# buttonboard-left.net
KiCad netlist of a schematic drawn in EAGLE
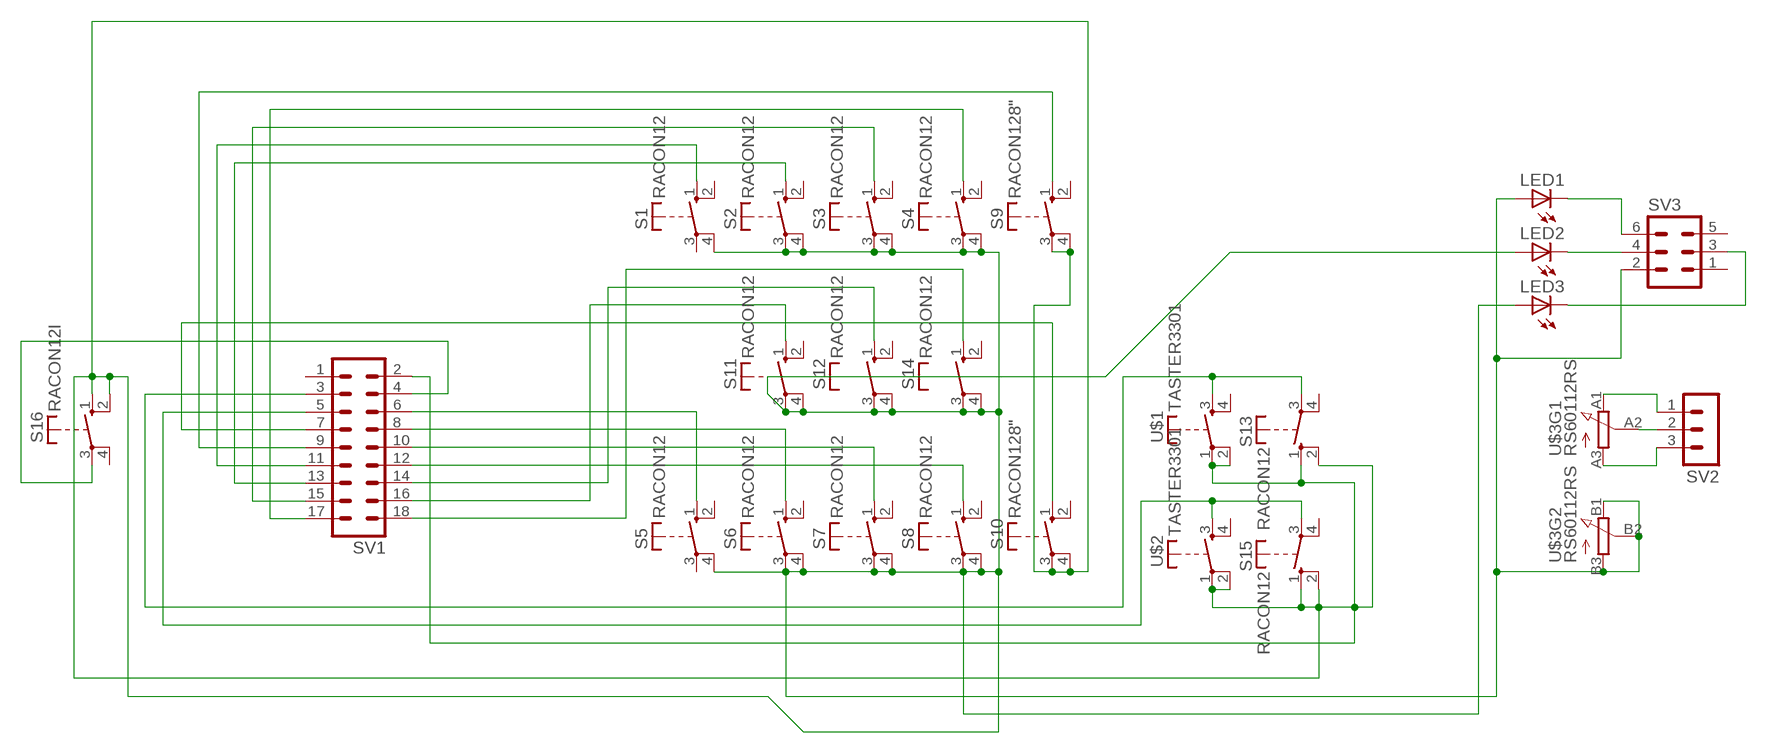
[diagram p0: schematic, sheet 1]

(export (version "E")
  (design (tool "Eeschema 10.0.6"))
  (components
    (comp (ref "LED1")
      (value "LED3MM")
      (footprint "eagle-import:LED3MM")
      (libsource (lib "eagle-import") (part "LED3MM"))
    )
    (comp (ref "LED2")
      (value "LED3MM")
      (footprint "eagle-import:LED3MM")
      (libsource (lib "eagle-import") (part "LED3MM"))
    )
    (comp (ref "LED3")
      (value "LED3MM")
      (footprint "eagle-import:LED3MM")
      (libsource (lib "eagle-import") (part "LED3MM"))
    )
    (comp (ref "S1")
      (value "RACON12")
      (footprint "eagle-import:RACON12")
      (libsource (lib "eagle-import") (part "RACON12"))
    )
    (comp (ref "S2")
      (value "RACON12")
      (footprint "eagle-import:RACON12")
      (libsource (lib "eagle-import") (part "RACON12"))
    )
    (comp (ref "S3")
      (value "RACON12")
      (footprint "eagle-import:RACON12")
      (libsource (lib "eagle-import") (part "RACON12"))
    )
    (comp (ref "S4")
      (value "RACON12")
      (footprint "eagle-import:RACON12")
      (libsource (lib "eagle-import") (part "RACON12"))
    )
    (comp (ref "S5")
      (value "RACON12")
      (footprint "eagle-import:RACON12")
      (libsource (lib "eagle-import") (part "RACON12"))
    )
    (comp (ref "S6")
      (value "RACON12")
      (footprint "eagle-import:RACON12")
      (libsource (lib "eagle-import") (part "RACON12"))
    )
    (comp (ref "S7")
      (value "RACON12")
      (footprint "eagle-import:RACON12")
      (libsource (lib "eagle-import") (part "RACON12"))
    )
    (comp (ref "S8")
      (value "RACON12")
      (footprint "eagle-import:RACON12")
      (libsource (lib "eagle-import") (part "RACON12"))
    )
    (comp (ref "S9")
      (value "RACON128\"")
      (footprint "eagle-import:RACON8")
      (libsource (lib "eagle-import") (part "RACON128{dblquote}"))
    )
    (comp (ref "S10")
      (value "RACON128\"")
      (footprint "eagle-import:RACON8")
      (libsource (lib "eagle-import") (part "RACON128{dblquote}"))
    )
    (comp (ref "S11")
      (value "RACON12")
      (footprint "eagle-import:RACON12")
      (libsource (lib "eagle-import") (part "RACON12"))
    )
    (comp (ref "S12")
      (value "RACON12")
      (footprint "eagle-import:RACON12")
      (libsource (lib "eagle-import") (part "RACON12"))
    )
    (comp (ref "S13")
      (value "RACON12")
      (footprint "eagle-import:RACON12")
      (libsource (lib "eagle-import") (part "RACON12"))
    )
    (comp (ref "S14")
      (value "RACON12")
      (footprint "eagle-import:RACON12")
      (libsource (lib "eagle-import") (part "RACON12"))
    )
    (comp (ref "S15")
      (value "RACON12")
      (footprint "eagle-import:RACON12")
      (libsource (lib "eagle-import") (part "RACON12"))
    )
    (comp (ref "S16")
      (value "RACON12I")
      (footprint "eagle-import:RACON12I")
      (libsource (lib "eagle-import") (part "RACON12I"))
    )
    (comp (ref "SV1")
      (value "MA09-2")
      (footprint "eagle-import:MA09-2")
      (libsource (lib "eagle-import") (part "MA09-2"))
    )
    (comp (ref "SV2")
      (value "MA03-1")
      (footprint "eagle-import:MA03-1")
      (libsource (lib "eagle-import") (part "MA03-1"))
    )
    (comp (ref "SV3")
      (value "MA03-2")
      (footprint "eagle-import:MA03-2")
      (libsource (lib "eagle-import") (part "MA03-2"))
    )
    (comp (ref "U$1")
      (value "TASTER3301")
      (footprint "eagle-import:3301")
      (libsource (lib "eagle-import") (part "TASTER3301"))
    )
    (comp (ref "U$2")
      (value "TASTER3301")
      (footprint "eagle-import:3301")
      (libsource (lib "eagle-import") (part "TASTER3301"))
    )
    (comp (ref "U$3")
      (value "RS60112RS")
      (footprint "eagle-import:RS60112")
      (libsource (lib "eagle-import") (part "RS60112RS"))
    )
  )
  (nets
    (net (code "1") (name "Net-(LED1-C)") (class "Default")
      (node (ref "LED1") (pin "K") (pinfunction "C_K") (pintype "passive"))
      (node (ref "SV3") (pin "6") (pinfunction "6_6") (pintype "passive"))
    )
    (net (code "2") (name "Net-(LED2-C)") (class "Default")
      (node (ref "LED2") (pin "K") (pinfunction "C_K") (pintype "passive"))
      (node (ref "SV3") (pin "4") (pinfunction "4_4") (pintype "passive"))
    )
    (net (code "3") (name "Net-(LED3-C)") (class "Default")
      (node (ref "LED3") (pin "K") (pinfunction "C_K") (pintype "passive"))
      (node (ref "SV3") (pin "3") (pinfunction "3_3") (pintype "passive"))
    )
    (net (code "4") (name "Net-(S1-S-Pad1)") (class "Default")
      (node (ref "S1") (pin "1") (pinfunction "S_1") (pintype "passive"))
      (node (ref "SV1") (pin "11") (pinfunction "11_11") (pintype "passive"))
    )
    (net (code "5") (name "Net-(S2-S-Pad1)") (class "Default")
      (node (ref "S2") (pin "1") (pinfunction "S_1") (pintype "passive"))
      (node (ref "SV1") (pin "13") (pinfunction "13_13") (pintype "passive"))
    )
    (net (code "6") (name "Net-(S3-S-Pad1)") (class "Default")
      (node (ref "S3") (pin "1") (pinfunction "S_1") (pintype "passive"))
      (node (ref "SV1") (pin "15") (pinfunction "15_15") (pintype "passive"))
    )
    (net (code "7") (name "Net-(S4-S-Pad1)") (class "Default")
      (node (ref "S4") (pin "1") (pinfunction "S_1") (pintype "passive"))
      (node (ref "SV1") (pin "17") (pinfunction "17_17") (pintype "passive"))
    )
    (net (code "8") (name "Net-(S5-S-Pad1)") (class "Default")
      (node (ref "S5") (pin "1") (pinfunction "S_1") (pintype "passive"))
      (node (ref "SV1") (pin "6") (pinfunction "6_6") (pintype "passive"))
    )
    (net (code "9") (name "Net-(S6-S-Pad1)") (class "Default")
      (node (ref "S6") (pin "1") (pinfunction "S_1") (pintype "passive"))
      (node (ref "SV1") (pin "8") (pinfunction "8_8") (pintype "passive"))
    )
    (net (code "10") (name "Net-(S7-S-Pad1)") (class "Default")
      (node (ref "S7") (pin "1") (pinfunction "S_1") (pintype "passive"))
      (node (ref "SV1") (pin "10") (pinfunction "10_10") (pintype "passive"))
    )
    (net (code "11") (name "Net-(S8-S-Pad1)") (class "Default")
      (node (ref "S8") (pin "1") (pinfunction "S_1") (pintype "passive"))
      (node (ref "SV1") (pin "12") (pinfunction "12_12") (pintype "passive"))
    )
    (net (code "12") (name "Net-(S9-S-Pad1)") (class "Default")
      (node (ref "S9") (pin "1") (pinfunction "S_1") (pintype "passive"))
      (node (ref "SV1") (pin "9") (pinfunction "9_9") (pintype "passive"))
    )
    (net (code "13") (name "Net-(S10-S-Pad1)") (class "Default")
      (node (ref "S10") (pin "1") (pinfunction "S_1") (pintype "passive"))
      (node (ref "SV1") (pin "7") (pinfunction "7_7") (pintype "passive"))
    )
    (net (code "14") (name "Net-(S11-S-Pad1)") (class "Default")
      (node (ref "S11") (pin "1") (pinfunction "S_1") (pintype "passive"))
      (node (ref "SV1") (pin "16") (pinfunction "16_16") (pintype "passive"))
    )
    (net (code "15") (name "Net-(S12-S-Pad1)") (class "Default")
      (node (ref "S12") (pin "1") (pinfunction "S_1") (pintype "passive"))
      (node (ref "SV1") (pin "14") (pinfunction "14_14") (pintype "passive"))
    )
    (net (code "16") (name "Net-(S13-P-Pad3)") (class "Default")
      (node (ref "S13") (pin "3") (pinfunction "P_3") (pintype "passive"))
      (node (ref "SV1") (pin "3") (pinfunction "3_3") (pintype "passive"))
      (node (ref "U$1") (pin "3") (pinfunction "S_3") (pintype "passive"))
    )
    (net (code "17") (name "Net-(S14-S-Pad1)") (class "Default")
      (node (ref "S14") (pin "1") (pinfunction "S_1") (pintype "passive"))
      (node (ref "SV1") (pin "18") (pinfunction "18_18") (pintype "passive"))
    )
    (net (code "18") (name "Net-(S15-P-Pad3)") (class "Default")
      (node (ref "S15") (pin "3") (pinfunction "P_3") (pintype "passive"))
      (node (ref "SV1") (pin "5") (pinfunction "5_5") (pintype "passive"))
      (node (ref "U$2") (pin "3") (pinfunction "S_3") (pintype "passive"))
    )
    (net (code "19") (name "Net-(S16-P-Pad3)") (class "Default")
      (node (ref "S16") (pin "3") (pinfunction "P_3") (pintype "passive"))
      (node (ref "SV1") (pin "4") (pinfunction "4_4") (pintype "passive"))
    )
    (net (code "20") (name "Net-(U$3A-A)") (class "Default")
      (node (ref "SV2") (pin "3") (pinfunction "3_3") (pintype "passive"))
      (node (ref "U$3") (pin "A3") (pinfunction "A_A3") (pintype "passive"))
    )
    (net (code "21") (name "Net-(U$3A-E)") (class "Default")
      (node (ref "SV2") (pin "1") (pinfunction "1_1") (pintype "passive"))
      (node (ref "U$3") (pin "A1") (pinfunction "E_A1") (pintype "passive"))
    )
    (net (code "22") (name "Net-(U$3A-S)") (class "Default")
      (node (ref "SV2") (pin "2") (pinfunction "2_2") (pintype "passive"))
      (node (ref "U$3") (pin "A2") (pinfunction "S_A2") (pintype "passive"))
    )
    (net (code "23") (name "Net-(U$3B-A)") (class "Default")
      (node (ref "LED1") (pin "A") (pinfunction "A_A") (pintype "passive"))
      (node (ref "LED2") (pin "A") (pinfunction "A_A") (pintype "passive"))
      (node (ref "LED3") (pin "A") (pinfunction "A_A") (pintype "passive"))
      (node (ref "S1") (pin "4") (pinfunction "P_4") (pintype "passive"))
      (node (ref "S10") (pin "3") (pinfunction "P_3") (pintype "passive"))
      (node (ref "S10") (pin "4") (pinfunction "P_4") (pintype "passive"))
      (node (ref "S11") (pin "3") (pinfunction "P_3") (pintype "passive"))
      (node (ref "S11") (pin "4") (pinfunction "P_4") (pintype "passive"))
      (node (ref "S12") (pin "3") (pinfunction "P_3") (pintype "passive"))
      (node (ref "S12") (pin "4") (pinfunction "P_4") (pintype "passive"))
      (node (ref "S13") (pin "1") (pinfunction "S_1") (pintype "passive"))
      (node (ref "S13") (pin "2") (pinfunction "S_2") (pintype "passive"))
      (node (ref "S14") (pin "3") (pinfunction "P_3") (pintype "passive"))
      (node (ref "S14") (pin "4") (pinfunction "P_4") (pintype "passive"))
      (node (ref "S15") (pin "1") (pinfunction "S_1") (pintype "passive"))
      (node (ref "S15") (pin "2") (pinfunction "S_2") (pintype "passive"))
      (node (ref "S16") (pin "1") (pinfunction "S_1") (pintype "passive"))
      (node (ref "S16") (pin "2") (pinfunction "S_2") (pintype "passive"))
      (node (ref "S2") (pin "3") (pinfunction "P_3") (pintype "passive"))
      (node (ref "S2") (pin "4") (pinfunction "P_4") (pintype "passive"))
      (node (ref "S3") (pin "3") (pinfunction "P_3") (pintype "passive"))
      (node (ref "S3") (pin "4") (pinfunction "P_4") (pintype "passive"))
      (node (ref "S4") (pin "3") (pinfunction "P_3") (pintype "passive"))
      (node (ref "S4") (pin "4") (pinfunction "P_4") (pintype "passive"))
      (node (ref "S5") (pin "4") (pinfunction "P_4") (pintype "passive"))
      (node (ref "S6") (pin "3") (pinfunction "P_3") (pintype "passive"))
      (node (ref "S6") (pin "4") (pinfunction "P_4") (pintype "passive"))
      (node (ref "S7") (pin "3") (pinfunction "P_3") (pintype "passive"))
      (node (ref "S7") (pin "4") (pinfunction "P_4") (pintype "passive"))
      (node (ref "S8") (pin "3") (pinfunction "P_3") (pintype "passive"))
      (node (ref "S8") (pin "4") (pinfunction "P_4") (pintype "passive"))
      (node (ref "S9") (pin "3") (pinfunction "P_3") (pintype "passive"))
      (node (ref "S9") (pin "4") (pinfunction "P_4") (pintype "passive"))
      (node (ref "SV1") (pin "2") (pinfunction "2_2") (pintype "passive"))
      (node (ref "SV3") (pin "2") (pinfunction "2_2") (pintype "passive"))
      (node (ref "U$1") (pin "1") (pinfunction "P_1") (pintype "passive"))
      (node (ref "U$1") (pin "2") (pinfunction "P_2") (pintype "passive"))
      (node (ref "U$2") (pin "1") (pinfunction "P_1") (pintype "passive"))
      (node (ref "U$2") (pin "2") (pinfunction "P_2") (pintype "passive"))
      (node (ref "U$3") (pin "B1") (pinfunction "E_B1") (pintype "passive"))
      (node (ref "U$3") (pin "B2") (pinfunction "S_B2") (pintype "passive"))
      (node (ref "U$3") (pin "B3") (pinfunction "A_B3") (pintype "passive"))
    )
    (net (code "24") (name "unconnected-(S1-P-Pad3)") (class "Default")
      (node (ref "S1") (pin "3") (pinfunction "P_3") (pintype "passive"))
    )
    (net (code "25") (name "unconnected-(S1-S-Pad2)") (class "Default")
      (node (ref "S1") (pin "2") (pinfunction "S_2") (pintype "passive"))
    )
    (net (code "26") (name "unconnected-(S2-S-Pad2)") (class "Default")
      (node (ref "S2") (pin "2") (pinfunction "S_2") (pintype "passive"))
    )
    (net (code "27") (name "unconnected-(S3-S-Pad2)") (class "Default")
      (node (ref "S3") (pin "2") (pinfunction "S_2") (pintype "passive"))
    )
    (net (code "28") (name "unconnected-(S4-S-Pad2)") (class "Default")
      (node (ref "S4") (pin "2") (pinfunction "S_2") (pintype "passive"))
    )
    (net (code "29") (name "unconnected-(S5-P-Pad3)") (class "Default")
      (node (ref "S5") (pin "3") (pinfunction "P_3") (pintype "passive"))
    )
    (net (code "30") (name "unconnected-(S5-S-Pad2)") (class "Default")
      (node (ref "S5") (pin "2") (pinfunction "S_2") (pintype "passive"))
    )
    (net (code "31") (name "unconnected-(S6-S-Pad2)") (class "Default")
      (node (ref "S6") (pin "2") (pinfunction "S_2") (pintype "passive"))
    )
    (net (code "32") (name "unconnected-(S7-S-Pad2)") (class "Default")
      (node (ref "S7") (pin "2") (pinfunction "S_2") (pintype "passive"))
    )
    (net (code "33") (name "unconnected-(S8-S-Pad2)") (class "Default")
      (node (ref "S8") (pin "2") (pinfunction "S_2") (pintype "passive"))
    )
    (net (code "34") (name "unconnected-(S9-S-Pad2)") (class "Default")
      (node (ref "S9") (pin "2") (pinfunction "S_2") (pintype "passive"))
    )
    (net (code "35") (name "unconnected-(S10-S-Pad2)") (class "Default")
      (node (ref "S10") (pin "2") (pinfunction "S_2") (pintype "passive"))
    )
    (net (code "36") (name "unconnected-(S11-S-Pad2)") (class "Default")
      (node (ref "S11") (pin "2") (pinfunction "S_2") (pintype "passive"))
    )
    (net (code "37") (name "unconnected-(S12-S-Pad2)") (class "Default")
      (node (ref "S12") (pin "2") (pinfunction "S_2") (pintype "passive"))
    )
    (net (code "38") (name "unconnected-(S13-P-Pad4)") (class "Default")
      (node (ref "S13") (pin "4") (pinfunction "P_4") (pintype "passive"))
    )
    (net (code "39") (name "unconnected-(S14-S-Pad2)") (class "Default")
      (node (ref "S14") (pin "2") (pinfunction "S_2") (pintype "passive"))
    )
    (net (code "40") (name "unconnected-(S15-P-Pad4)") (class "Default")
      (node (ref "S15") (pin "4") (pinfunction "P_4") (pintype "passive"))
    )
    (net (code "41") (name "unconnected-(S16-P-Pad4)") (class "Default")
      (node (ref "S16") (pin "4") (pinfunction "P_4") (pintype "passive"))
    )
    (net (code "42") (name "unconnected-(SV1-Pad1)") (class "Default")
      (node (ref "SV1") (pin "1") (pinfunction "1_1") (pintype "passive"))
    )
    (net (code "43") (name "unconnected-(SV3-Pad1)") (class "Default")
      (node (ref "SV3") (pin "1") (pinfunction "1_1") (pintype "passive"))
    )
    (net (code "44") (name "unconnected-(SV3-Pad5)") (class "Default")
      (node (ref "SV3") (pin "5") (pinfunction "5_5") (pintype "passive"))
    )
    (net (code "45") (name "unconnected-(U$1-S-Pad4)") (class "Default")
      (node (ref "U$1") (pin "4") (pinfunction "S_4") (pintype "passive"))
    )
    (net (code "46") (name "unconnected-(U$2-S-Pad4)") (class "Default")
      (node (ref "U$2") (pin "4") (pinfunction "S_4") (pintype "passive"))
    )
  )
)
